# esp32s3.net
KiCad netlist of a schematic drawn in Altium Designer
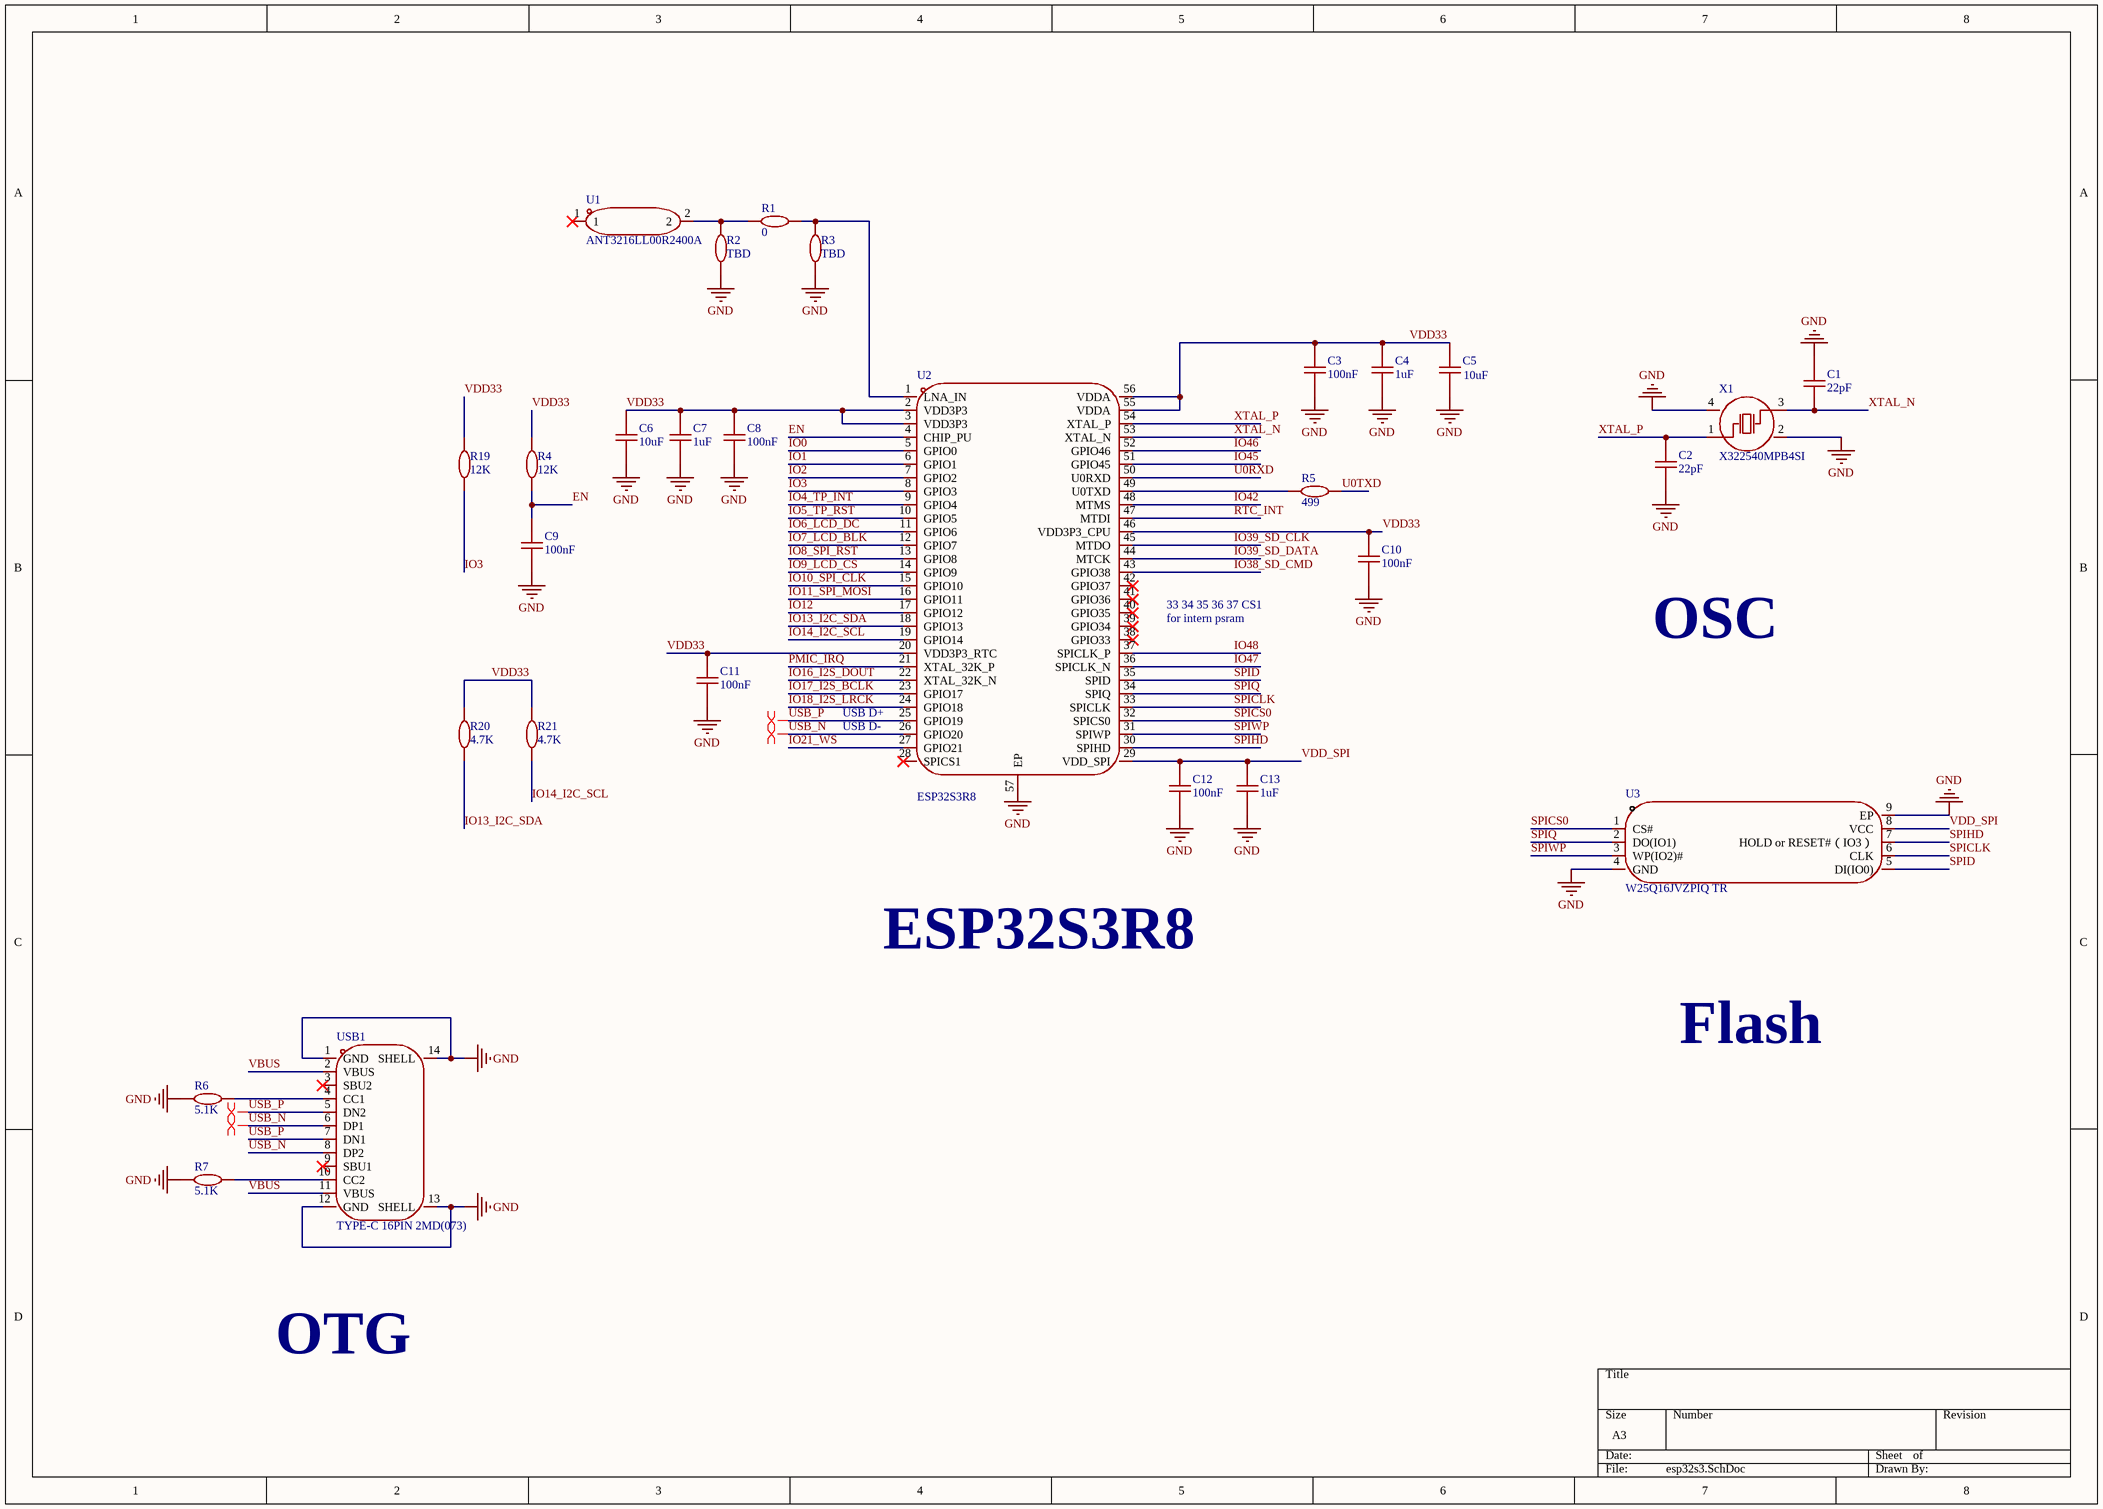
[diagram p0: esp32s3.SchDoc]

(export (version "E")
  (design (tool "Eeschema 10.0.6"))
  (components
    (comp (ref "C1") (value "22pF") (footprint "C0402") (libsource (lib "RLC") (part "C0402")))
    (comp (ref "C2") (value "22pF") (footprint "C0402") (libsource (lib "RLC") (part "C0402")))
    (comp (ref "C3") (value "100nF") (footprint "C0402") (libsource (lib "RLC") (part "C0402")))
    (comp (ref "C4") (value "1uF") (footprint "C0402") (libsource (lib "RLC") (part "C0402")))
    (comp (ref "C5") (value "10uF") (footprint "C0603") (libsource (lib "RLC") (part "C0603")))
    (comp (ref "C6") (value "10uF") (footprint "C0603") (libsource (lib "RLC") (part "C0603")))
    (comp (ref "C7") (value "1uF") (footprint "C0402") (libsource (lib "RLC") (part "C0402")))
    (comp (ref "C8") (value "100nF") (footprint "C0402") (libsource (lib "RLC") (part "C0402")))
    (comp (ref "C9") (value "100nF") (footprint "C0402") (libsource (lib "RLC") (part "C0402")))
    (comp (ref "C10") (value "100nF") (footprint "C0402") (libsource (lib "RLC") (part "C0402")))
    (comp (ref "C11") (value "100nF") (footprint "C0402") (libsource (lib "RLC") (part "C0402")))
    (comp (ref "C12") (value "100nF") (footprint "C0402") (libsource (lib "RLC") (part "C0402")))
    (comp (ref "C13") (value "1uF") (footprint "C0402") (libsource (lib "RLC") (part "C0402")))
    (comp (ref "R1") (value "0") (footprint "R0402") (libsource (lib "RLC") (part "R0402")))
    (comp (ref "R2") (value "TBD") (footprint "R0402") (libsource (lib "RLC") (part "R0402")))
    (comp (ref "R3") (value "TBD") (footprint "R0402") (libsource (lib "RLC") (part "R0402")))
    (comp (ref "R4") (value "12K") (footprint "R0402") (libsource (lib "RLC") (part "R0402")))
    (comp (ref "R5") (value "499") (footprint "R0402") (libsource (lib "RLC") (part "R0402")))
    (comp (ref "R6") (value "5.1K") (footprint "R0402") (libsource (lib "RLC") (part "R0402")))
    (comp (ref "R7") (value "5.1K") (footprint "R0402") (libsource (lib "RLC") (part "R0402")))
    (comp (ref "R19") (value "12K") (footprint "R0402") (libsource (lib "RLC") (part "R0402")))
    (comp (ref "R20") (value "4.7K") (footprint "R0402") (libsource (lib "RLC") (part "R0402")))
    (comp (ref "R21") (value "4.7K") (footprint "R0402") (libsource (lib "RLC") (part "R0402")))
    (comp (ref "U1")
      (value "ANT3216LL00R2400A")
      (footprint "ANT-SMD_L3.2-W1.6")
      (libsource (lib "ANT") (part "ANT3216LL00R2400A"))
    )
    (comp (ref "U2")
      (value "ESP32S3R8")
      (footprint "QFN-56_L7.0-W7.0-P0.40-TL-EP4.0")
      (libsource (lib "IC") (part "ESP32S3R8"))
    )
    (comp (ref "U3")
      (value "W25Q16JVZPIQ TR")
      (footprint "WSON-8_L6.0-W5.0-P1.27-BL-EP")
      (libsource (lib "IC") (part "W25Q16JVZPIQ TR"))
    )
    (comp (ref "USB1")
      (value "TYPE-C 16PIN 2MD(073)")
      (footprint "USB-C-SMD_TYPE-C-6PIN-2MD-073")
      (libsource (lib "Connector") (part "TYPE-C 16PIN 2MD(073)"))
    )
    (comp (ref "X1")
      (value "X322540MPB4SI")
      (footprint "OSC-SMD_4P-L3.2-W2.5-BL_SIT8008BI")
      (libsource (lib "OSC") (part "X322540MPB4SI"))
    )
  )
  (nets
    (net (code "1") (name "/EN") (class "Default")
      (node (ref "C9") (pin "2") (pinfunction "2_2") (pintype "passive"))
      (node (ref "R4") (pin "1") (pinfunction "1_1") (pintype "passive"))
      (node (ref "U2") (pin "4") (pinfunction "CHIP_PU_4") (pintype "passive"))
    )
    (net (code "2") (name "/IO0") (class "Default")
      (node (ref "U2") (pin "5") (pinfunction "GPIO0_5") (pintype "passive"))
    )
    (net (code "3") (name "/IO1") (class "Default")
      (node (ref "U2") (pin "6") (pinfunction "GPIO1_6") (pintype "passive"))
    )
    (net (code "4") (name "/IO2") (class "Default")
      (node (ref "U2") (pin "7") (pinfunction "GPIO2_7") (pintype "passive"))
    )
    (net (code "5") (name "/IO3") (class "Default")
      (node (ref "R19") (pin "1") (pinfunction "1_1") (pintype "passive"))
      (node (ref "U2") (pin "8") (pinfunction "GPIO3_8") (pintype "passive"))
    )
    (net (code "6") (name "/IO4_TP_INT") (class "Default")
      (node (ref "U2") (pin "9") (pinfunction "GPIO4_9") (pintype "passive"))
    )
    (net (code "7") (name "/IO5_TP_RST") (class "Default")
      (node (ref "U2") (pin "10") (pinfunction "GPIO5_10") (pintype "passive"))
    )
    (net (code "8") (name "/IO6_LCD_DC") (class "Default")
      (node (ref "U2") (pin "11") (pinfunction "GPIO6_11") (pintype "passive"))
    )
    (net (code "9") (name "/IO7_LCD_BLK") (class "Default")
      (node (ref "U2") (pin "12") (pinfunction "GPIO7_12") (pintype "passive"))
    )
    (net (code "10") (name "/IO8_SPI_RST") (class "Default")
      (node (ref "U2") (pin "13") (pinfunction "GPIO8_13") (pintype "passive"))
    )
    (net (code "11") (name "/IO9_LCD_CS") (class "Default")
      (node (ref "U2") (pin "14") (pinfunction "GPIO9_14") (pintype "passive"))
    )
    (net (code "12") (name "/IO10_SPI_CLK") (class "Default")
      (node (ref "U2") (pin "15") (pinfunction "GPIO10_15") (pintype "passive"))
    )
    (net (code "13") (name "/IO11_SPI_MOSI") (class "Default")
      (node (ref "U2") (pin "16") (pinfunction "GPIO11_16") (pintype "passive"))
    )
    (net (code "14") (name "/IO12") (class "Default")
      (node (ref "U2") (pin "17") (pinfunction "GPIO12_17") (pintype "passive"))
    )
    (net (code "15") (name "/IO13_I2C_SDA") (class "Default")
      (node (ref "R20") (pin "1") (pinfunction "1_1") (pintype "passive"))
      (node (ref "U2") (pin "18") (pinfunction "GPIO13_18") (pintype "passive"))
    )
    (net (code "16") (name "/IO14_I2C_SCL") (class "Default")
      (node (ref "R21") (pin "1") (pinfunction "1_1") (pintype "passive"))
      (node (ref "U2") (pin "19") (pinfunction "GPIO14_19") (pintype "passive"))
    )
    (net (code "17") (name "/IO16_I2S_DOUT") (class "Default")
      (node (ref "U2") (pin "22") (pinfunction "XTAL_32K_N_22") (pintype "passive"))
    )
    (net (code "18") (name "/IO17_I2S_BCLK") (class "Default")
      (node (ref "U2") (pin "23") (pinfunction "GPIO17_23") (pintype "passive"))
    )
    (net (code "19") (name "/IO18_I2S_LRCK") (class "Default")
      (node (ref "U2") (pin "24") (pinfunction "GPIO18_24") (pintype "passive"))
    )
    (net (code "20") (name "/IO21_WS") (class "Default")
      (node (ref "U2") (pin "27") (pinfunction "GPIO21_27") (pintype "passive"))
    )
    (net (code "21") (name "/IO38_SD_CMD") (class "Default")
      (node (ref "U2") (pin "43") (pinfunction "GPIO38_43") (pintype "passive"))
    )
    (net (code "22") (name "/IO39_SD_CLK") (class "Default")
      (node (ref "U2") (pin "45") (pinfunction "MTDO_45") (pintype "passive"))
    )
    (net (code "23") (name "/IO39_SD_DATA") (class "Default")
      (node (ref "U2") (pin "44") (pinfunction "MTCK_44") (pintype "passive"))
    )
    (net (code "24") (name "/IO42") (class "Default")
      (node (ref "U2") (pin "48") (pinfunction "MTMS_48") (pintype "passive"))
    )
    (net (code "25") (name "/IO45") (class "Default")
      (node (ref "U2") (pin "51") (pinfunction "GPIO45_51") (pintype "passive"))
    )
    (net (code "26") (name "/IO46") (class "Default")
      (node (ref "U2") (pin "52") (pinfunction "GPIO46_52") (pintype "passive"))
    )
    (net (code "27") (name "/IO47") (class "Default")
      (node (ref "U2") (pin "36") (pinfunction "SPICLK_N_36") (pintype "passive"))
    )
    (net (code "28") (name "/IO48") (class "Default")
      (node (ref "U2") (pin "37") (pinfunction "SPICLK_P_37") (pintype "passive"))
    )
    (net (code "29") (name "/PMIC_IRQ") (class "Default")
      (node (ref "U2") (pin "21") (pinfunction "XTAL_32K_P_21") (pintype "passive"))
    )
    (net (code "30") (name "/RTC_INT") (class "Default")
      (node (ref "U2") (pin "47") (pinfunction "MTDI_47") (pintype "passive"))
    )
    (net (code "31") (name "/SPICLK") (class "Default")
      (node (ref "U2") (pin "33") (pinfunction "SPICLK_33") (pintype "passive"))
      (node (ref "U3") (pin "6") (pinfunction "CLK_6") (pintype "passive"))
    )
    (net (code "32") (name "/SPICS0") (class "Default")
      (node (ref "U2") (pin "32") (pinfunction "SPICS0_32") (pintype "passive"))
      (node (ref "U3") (pin "1") (pinfunction "CS#_1") (pintype "passive"))
    )
    (net (code "33") (name "/SPID") (class "Default")
      (node (ref "U2") (pin "35") (pinfunction "SPID_35") (pintype "passive"))
      (node (ref "U3") (pin "5") (pinfunction "DI(IO0)_5") (pintype "passive"))
    )
    (net (code "34") (name "/SPIHD") (class "Default")
      (node (ref "U2") (pin "30") (pinfunction "SPIHD_30") (pintype "passive"))
      (node (ref "U3") (pin "7") (pinfunction "HOLD_or_RESET#（IO3）_7") (pintype "passive"))
    )
    (net (code "35") (name "/SPIQ") (class "Default")
      (node (ref "U2") (pin "34") (pinfunction "SPIQ_34") (pintype "passive"))
      (node (ref "U3") (pin "2") (pinfunction "DO(IO1)_2") (pintype "passive"))
    )
    (net (code "36") (name "/SPIWP") (class "Default")
      (node (ref "U2") (pin "31") (pinfunction "SPIWP_31") (pintype "passive"))
      (node (ref "U3") (pin "3") (pinfunction "WP(IO2)#_3") (pintype "passive"))
    )
    (net (code "37") (name "/U0RXD") (class "Default")
      (node (ref "U2") (pin "50") (pinfunction "U0RXD_50") (pintype "passive"))
    )
    (net (code "38") (name "/U0TXD") (class "Default")
      (node (ref "R5") (pin "2") (pinfunction "2_2") (pintype "passive"))
    )
    (net (code "39") (name "/USB_N") (class "Default")
      (node (ref "U2") (pin "26") (pinfunction "GPIO20_26") (pintype "passive"))
      (node (ref "USB1") (pin "6") (pinfunction "DP1_6") (pintype "passive"))
      (node (ref "USB1") (pin "8") (pinfunction "DP2_8") (pintype "passive"))
    )
    (net (code "40") (name "/USB_P") (class "Default")
      (node (ref "U2") (pin "25") (pinfunction "GPIO19_25") (pintype "passive"))
      (node (ref "USB1") (pin "5") (pinfunction "DN2_5") (pintype "passive"))
      (node (ref "USB1") (pin "7") (pinfunction "DN1_7") (pintype "passive"))
    )
    (net (code "41") (name "/VBUS") (class "Default")
      (node (ref "USB1") (pin "11") (pinfunction "VBUS_11") (pintype "passive"))
      (node (ref "USB1") (pin "2") (pinfunction "VBUS_2") (pintype "passive"))
    )
    (net (code "42") (name "/VDD33") (class "Default")
      (node (ref "C10") (pin "2") (pinfunction "2_2") (pintype "passive"))
      (node (ref "C11") (pin "2") (pinfunction "2_2") (pintype "passive"))
      (node (ref "C3") (pin "2") (pinfunction "2_2") (pintype "passive"))
      (node (ref "C4") (pin "2") (pinfunction "2_2") (pintype "passive"))
      (node (ref "C5") (pin "2") (pinfunction "2_2") (pintype "passive"))
      (node (ref "C6") (pin "2") (pinfunction "2_2") (pintype "passive"))
      (node (ref "C7") (pin "2") (pinfunction "2_2") (pintype "passive"))
      (node (ref "C8") (pin "2") (pinfunction "2_2") (pintype "passive"))
      (node (ref "R19") (pin "2") (pinfunction "2_2") (pintype "passive"))
      (node (ref "R20") (pin "2") (pinfunction "2_2") (pintype "passive"))
      (node (ref "R21") (pin "2") (pinfunction "2_2") (pintype "passive"))
      (node (ref "R4") (pin "2") (pinfunction "2_2") (pintype "passive"))
      (node (ref "U2") (pin "2") (pinfunction "VDD3P3_2") (pintype "passive"))
      (node (ref "U2") (pin "20") (pinfunction "VDD3P3_RTC_20") (pintype "passive"))
      (node (ref "U2") (pin "3") (pinfunction "VDD3P3_3") (pintype "passive"))
      (node (ref "U2") (pin "46") (pinfunction "VDD3P3_CPU_46") (pintype "passive"))
      (node (ref "U2") (pin "55") (pinfunction "VDDA_55") (pintype "passive"))
      (node (ref "U2") (pin "56") (pinfunction "VDDA_56") (pintype "passive"))
    )
    (net (code "43") (name "/VDD_SPI") (class "Default")
      (node (ref "C12") (pin "2") (pinfunction "2_2") (pintype "passive"))
      (node (ref "C13") (pin "2") (pinfunction "2_2") (pintype "passive"))
      (node (ref "U2") (pin "29") (pinfunction "VDD_SPI_29") (pintype "passive"))
      (node (ref "U3") (pin "8") (pinfunction "VCC_8") (pintype "passive"))
    )
    (net (code "44") (name "/XTAL_N") (class "Default")
      (node (ref "C1") (pin "1") (pinfunction "1_1") (pintype "passive"))
      (node (ref "U2") (pin "53") (pinfunction "XTAL_N_53") (pintype "passive"))
      (node (ref "X1") (pin "3") (pinfunction "OSC2_3") (pintype "passive"))
    )
    (net (code "45") (name "/XTAL_P") (class "Default")
      (node (ref "C2") (pin "2") (pinfunction "2_2") (pintype "passive"))
      (node (ref "U2") (pin "54") (pinfunction "XTAL_P_54") (pintype "passive"))
      (node (ref "X1") (pin "1") (pinfunction "OSC1_1") (pintype "passive"))
    )
    (net (code "46") (name "GND") (class "Default")
      (node (ref "C1") (pin "2") (pinfunction "2_2") (pintype "passive"))
      (node (ref "C10") (pin "1") (pinfunction "1_1") (pintype "passive"))
      (node (ref "C11") (pin "1") (pinfunction "1_1") (pintype "passive"))
      (node (ref "C12") (pin "1") (pinfunction "1_1") (pintype "passive"))
      (node (ref "C13") (pin "1") (pinfunction "1_1") (pintype "passive"))
      (node (ref "C2") (pin "1") (pinfunction "1_1") (pintype "passive"))
      (node (ref "C3") (pin "1") (pinfunction "1_1") (pintype "passive"))
      (node (ref "C4") (pin "1") (pinfunction "1_1") (pintype "passive"))
      (node (ref "C5") (pin "1") (pinfunction "1_1") (pintype "passive"))
      (node (ref "C6") (pin "1") (pinfunction "1_1") (pintype "passive"))
      (node (ref "C7") (pin "1") (pinfunction "1_1") (pintype "passive"))
      (node (ref "C8") (pin "1") (pinfunction "1_1") (pintype "passive"))
      (node (ref "C9") (pin "1") (pinfunction "1_1") (pintype "passive"))
      (node (ref "R2") (pin "1") (pinfunction "1_1") (pintype "passive"))
      (node (ref "R3") (pin "1") (pinfunction "1_1") (pintype "passive"))
      (node (ref "R6") (pin "2") (pinfunction "2_2") (pintype "passive"))
      (node (ref "R7") (pin "2") (pinfunction "2_2") (pintype "passive"))
      (node (ref "U2") (pin "57") (pinfunction "EP_57") (pintype "passive"))
      (node (ref "U3") (pin "4") (pinfunction "GND_4") (pintype "passive"))
      (node (ref "U3") (pin "9") (pinfunction "EP_9") (pintype "passive"))
      (node (ref "USB1") (pin "1") (pinfunction "GND_1") (pintype "passive"))
      (node (ref "USB1") (pin "12") (pinfunction "GND_12") (pintype "passive"))
      (node (ref "USB1") (pin "13") (pinfunction "SHELL_13") (pintype "passive"))
      (node (ref "USB1") (pin "14") (pinfunction "SHELL_14") (pintype "passive"))
      (node (ref "X1") (pin "2") (pinfunction "GND_2") (pintype "passive"))
      (node (ref "X1") (pin "4") (pinfunction "GND_4") (pintype "passive"))
    )
    (net (code "47") (name "Net-(R1-Pad1)") (class "Default")
      (node (ref "R1") (pin "1") (pinfunction "1_1") (pintype "passive"))
      (node (ref "R2") (pin "2") (pinfunction "2_2") (pintype "passive"))
      (node (ref "U1") (pin "2") (pinfunction "2_2") (pintype "passive"))
    )
    (net (code "48") (name "Net-(U2-LNA_IN)") (class "Default")
      (node (ref "R1") (pin "2") (pinfunction "2_2") (pintype "passive"))
      (node (ref "R3") (pin "2") (pinfunction "2_2") (pintype "passive"))
      (node (ref "U2") (pin "1") (pinfunction "LNA_IN_1") (pintype "passive"))
    )
    (net (code "49") (name "Net-(U2-U0TXD)") (class "Default")
      (node (ref "R5") (pin "1") (pinfunction "1_1") (pintype "passive"))
      (node (ref "U2") (pin "49") (pinfunction "U0TXD_49") (pintype "passive"))
    )
    (net (code "50") (name "Net-(USB1-CC1)") (class "Default")
      (node (ref "R6") (pin "1") (pinfunction "1_1") (pintype "passive"))
      (node (ref "USB1") (pin "4") (pinfunction "CC1_4") (pintype "passive"))
    )
    (net (code "51") (name "Net-(USB1-CC2)") (class "Default")
      (node (ref "R7") (pin "1") (pinfunction "1_1") (pintype "passive"))
      (node (ref "USB1") (pin "10") (pinfunction "CC2_10") (pintype "passive"))
    )
    (net (code "52") (name "unconnected-(U1-Pad1)") (class "Default")
      (node (ref "U1") (pin "1") (pinfunction "1_1") (pintype "passive+no_connect"))
    )
    (net (code "53") (name "unconnected-(U2-GPIO33-Pad38)") (class "Default")
      (node (ref "U2") (pin "38") (pinfunction "GPIO33_38") (pintype "passive+no_connect"))
    )
    (net (code "54") (name "unconnected-(U2-GPIO34-Pad39)") (class "Default")
      (node (ref "U2") (pin "39") (pinfunction "GPIO34_39") (pintype "passive+no_connect"))
    )
    (net (code "55") (name "unconnected-(U2-GPIO35-Pad40)") (class "Default")
      (node (ref "U2") (pin "40") (pinfunction "GPIO35_40") (pintype "passive+no_connect"))
    )
    (net (code "56") (name "unconnected-(U2-GPIO36-Pad41)") (class "Default")
      (node (ref "U2") (pin "41") (pinfunction "GPIO36_41") (pintype "passive+no_connect"))
    )
    (net (code "57") (name "unconnected-(U2-GPIO37-Pad42)") (class "Default")
      (node (ref "U2") (pin "42") (pinfunction "GPIO37_42") (pintype "passive+no_connect"))
    )
    (net (code "58") (name "unconnected-(U2-SPICS1-Pad28)") (class "Default")
      (node (ref "U2") (pin "28") (pinfunction "SPICS1_28") (pintype "passive+no_connect"))
    )
    (net (code "59") (name "unconnected-(USB1-SBU1-Pad9)") (class "Default")
      (node (ref "USB1") (pin "9") (pinfunction "SBU1_9") (pintype "passive+no_connect"))
    )
    (net (code "60") (name "unconnected-(USB1-SBU2-Pad3)") (class "Default")
      (node (ref "USB1") (pin "3") (pinfunction "SBU2_3") (pintype "passive+no_connect"))
    )
  )
)
